# deployment.net
KiCad netlist of a schematic drawn in EAGLE
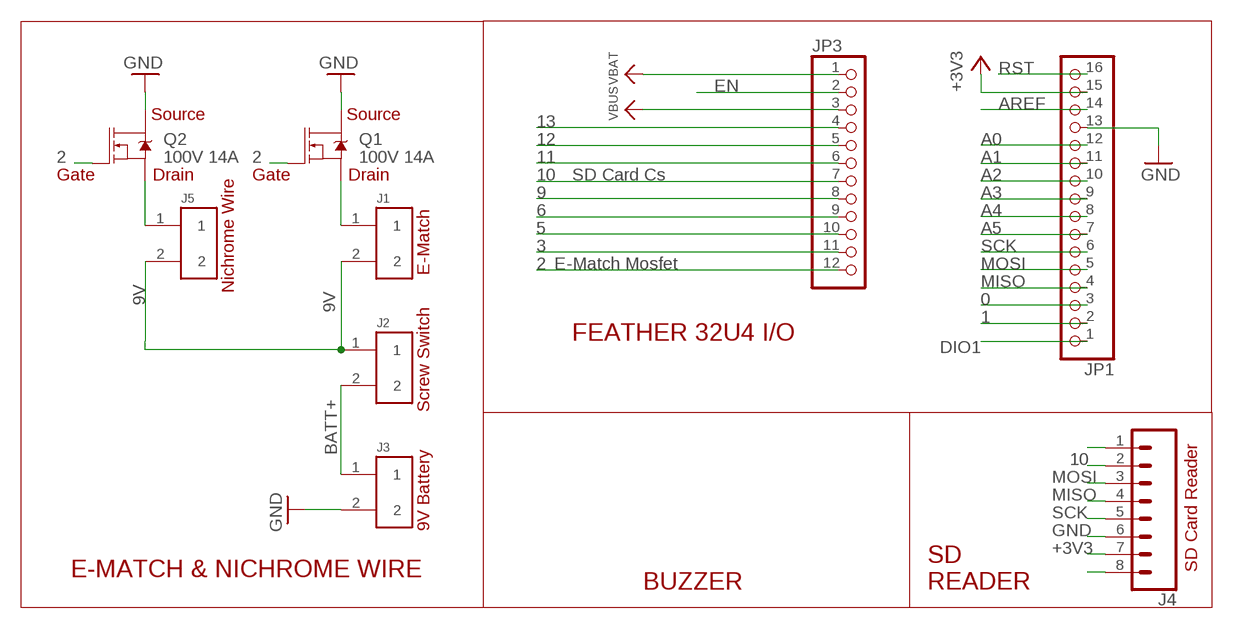
[diagram p0: schematic, sheet 1]

(export (version "E")
  (design (tool "Eeschema 10.0.6"))
  (components
    (comp (ref "J1")
      (value "1935161")
      (footprint "eagle-import:PHOENIX_1935161")
      (fields (field (name "DIGI-KEY_PART_NUMBER") "277-1667-ND") (field (name "MF") "Phoenix Contact"))
      (libsource (lib "eagle-import") (part "1935161"))
    )
    (comp (ref "J2")
      (value "1935161")
      (footprint "eagle-import:PHOENIX_1935161")
      (fields (field (name "DIGI-KEY_PART_NUMBER") "277-1667-ND") (field (name "MF") "Phoenix Contact"))
      (libsource (lib "eagle-import") (part "1935161"))
    )
    (comp (ref "J3")
      (value "1935161")
      (footprint "eagle-import:PHOENIX_1935161")
      (fields (field (name "DIGI-KEY_PART_NUMBER") "277-1667-ND") (field (name "MF") "Phoenix Contact"))
      (libsource (lib "eagle-import") (part "1935161"))
    )
    (comp (ref "J4")
      (value "CONN_08\"")
      (footprint "eagle-import:1X08")
      (libsource (lib "eagle-import") (part "CONN_08{dblquote}"))
    )
    (comp (ref "J5")
      (value "1935161")
      (footprint "eagle-import:PHOENIX_1935161")
      (fields (field (name "DIGI-KEY_PART_NUMBER") "277-1667-ND") (field (name "MF") "Phoenix Contact"))
      (libsource (lib "eagle-import") (part "1935161"))
    )
    (comp (ref "JP1")
      (value "HEADER-1X16ROUND")
      (footprint "eagle-import:1X16_ROUND")
      (libsource (lib "eagle-import") (part "HEADER-1X16ROUND"))
    )
    (comp (ref "JP3")
      (value "HEADER-1X12")
      (footprint "eagle-import:1X12_ROUND")
      (libsource (lib "eagle-import") (part "HEADER-1X12"))
    )
    (comp (ref "Q1")
      (value "100V 14A")
      (footprint "eagle-import:TO220V")
      (libsource (lib "eagle-import") (part "MOSFET-NCH-FQP30N06L"))
    )
    (comp (ref "Q2")
      (value "100V 14A")
      (footprint "eagle-import:TO220V")
      (libsource (lib "eagle-import") (part "MOSFET-NCH-FQP30N06L"))
    )
  )
  (nets
    (net (code "1") (name "+3V3") (class "Default")
      (node (ref "J4") (pin "7") (pinfunction "7_7") (pintype "passive"))
      (node (ref "JP1") (pin "15") (pinfunction "15_15") (pintype "passive"))
    )
    (net (code "2") (name "/0") (class "Default")
      (node (ref "JP1") (pin "3") (pinfunction "3_3") (pintype "passive"))
    )
    (net (code "3") (name "/1") (class "Default")
      (node (ref "JP1") (pin "2") (pinfunction "2_2") (pintype "passive"))
    )
    (net (code "4") (name "/2") (class "Default")
      (node (ref "JP3") (pin "12") (pinfunction "12_12") (pintype "passive"))
      (node (ref "Q1") (pin "1") (pinfunction "G_1") (pintype "bidirectional"))
      (node (ref "Q2") (pin "1") (pinfunction "G_1") (pintype "bidirectional"))
    )
    (net (code "5") (name "/3") (class "Default")
      (node (ref "JP3") (pin "11") (pinfunction "11_11") (pintype "passive"))
    )
    (net (code "6") (name "/5") (class "Default")
      (node (ref "JP3") (pin "10") (pinfunction "10_10") (pintype "passive"))
    )
    (net (code "7") (name "/6") (class "Default")
      (node (ref "JP3") (pin "9") (pinfunction "9_9") (pintype "passive"))
    )
    (net (code "8") (name "/9") (class "Default")
      (node (ref "JP3") (pin "8") (pinfunction "8_8") (pintype "passive"))
    )
    (net (code "9") (name "/9V") (class "Default")
      (node (ref "J1") (pin "2") (pinfunction "2_2") (pintype "passive"))
      (node (ref "J2") (pin "1") (pinfunction "1_1") (pintype "passive"))
      (node (ref "J5") (pin "2") (pinfunction "2_2") (pintype "passive"))
    )
    (net (code "10") (name "/10") (class "Default")
      (node (ref "J4") (pin "1") (pinfunction "1_1") (pintype "passive"))
      (node (ref "J4") (pin "2") (pinfunction "2_2") (pintype "passive"))
      (node (ref "JP3") (pin "7") (pinfunction "7_7") (pintype "passive"))
    )
    (net (code "11") (name "/11") (class "Default")
      (node (ref "JP3") (pin "6") (pinfunction "6_6") (pintype "passive"))
    )
    (net (code "12") (name "/12") (class "Default")
      (node (ref "JP3") (pin "5") (pinfunction "5_5") (pintype "passive"))
    )
    (net (code "13") (name "/13") (class "Default")
      (node (ref "JP3") (pin "4") (pinfunction "4_4") (pintype "passive"))
    )
    (net (code "14") (name "/A0") (class "Default")
      (node (ref "JP1") (pin "12") (pinfunction "12_12") (pintype "passive"))
    )
    (net (code "15") (name "/A1") (class "Default")
      (node (ref "JP1") (pin "11") (pinfunction "11_11") (pintype "passive"))
    )
    (net (code "16") (name "/A2") (class "Default")
      (node (ref "JP1") (pin "10") (pinfunction "10_10") (pintype "passive"))
    )
    (net (code "17") (name "/A3") (class "Default")
      (node (ref "JP1") (pin "9") (pinfunction "9_9") (pintype "passive"))
    )
    (net (code "18") (name "/A4") (class "Default")
      (node (ref "JP1") (pin "8") (pinfunction "8_8") (pintype "passive"))
    )
    (net (code "19") (name "/A5") (class "Default")
      (node (ref "JP1") (pin "7") (pinfunction "7_7") (pintype "passive"))
    )
    (net (code "20") (name "/AREF") (class "Default")
      (node (ref "JP1") (pin "14") (pinfunction "14_14") (pintype "passive"))
    )
    (net (code "21") (name "/BATT+") (class "Default")
      (node (ref "J2") (pin "2") (pinfunction "2_2") (pintype "passive"))
      (node (ref "J3") (pin "1") (pinfunction "1_1") (pintype "passive"))
    )
    (net (code "22") (name "/DIO1") (class "Default")
      (node (ref "JP1") (pin "1") (pinfunction "1_1") (pintype "passive"))
    )
    (net (code "23") (name "/EN") (class "Default")
      (node (ref "JP3") (pin "2") (pinfunction "2_2") (pintype "passive"))
    )
    (net (code "24") (name "/MISO") (class "Default")
      (node (ref "J4") (pin "4") (pinfunction "4_4") (pintype "passive"))
      (node (ref "JP1") (pin "4") (pinfunction "4_4") (pintype "passive"))
    )
    (net (code "25") (name "/MOSI") (class "Default")
      (node (ref "J4") (pin "3") (pinfunction "3_3") (pintype "passive"))
      (node (ref "JP1") (pin "5") (pinfunction "5_5") (pintype "passive"))
    )
    (net (code "26") (name "/RST") (class "Default")
      (node (ref "JP1") (pin "16") (pinfunction "16_16") (pintype "passive"))
    )
    (net (code "27") (name "/SCK") (class "Default")
      (node (ref "J4") (pin "5") (pinfunction "5_5") (pintype "passive"))
      (node (ref "JP1") (pin "6") (pinfunction "6_6") (pintype "passive"))
    )
    (net (code "28") (name "GND") (class "Default")
      (node (ref "J3") (pin "2") (pinfunction "2_2") (pintype "passive"))
      (node (ref "J4") (pin "6") (pinfunction "6_6") (pintype "passive"))
      (node (ref "JP1") (pin "13") (pinfunction "13_13") (pintype "passive"))
      (node (ref "Q1") (pin "2") (pinfunction "D_2") (pintype "bidirectional"))
      (node (ref "Q2") (pin "2") (pinfunction "D_2") (pintype "bidirectional"))
    )
    (net (code "29") (name "Net-(Q1-S)") (class "Default")
      (node (ref "J1") (pin "1") (pinfunction "1_1") (pintype "passive"))
      (node (ref "Q1") (pin "3") (pinfunction "S_3") (pintype "bidirectional"))
    )
    (net (code "30") (name "Net-(Q2-S)") (class "Default")
      (node (ref "J5") (pin "1") (pinfunction "1_1") (pintype "passive"))
      (node (ref "Q2") (pin "3") (pinfunction "S_3") (pintype "bidirectional"))
    )
    (net (code "31") (name "VBAT") (class "Default")
      (node (ref "JP3") (pin "1") (pinfunction "1_1") (pintype "passive"))
    )
    (net (code "32") (name "VBUS") (class "Default")
      (node (ref "JP3") (pin "3") (pinfunction "3_3") (pintype "passive"))
    )
    (net (code "33") (name "unconnected-(J4-Pad8)") (class "Default")
      (node (ref "J4") (pin "8") (pinfunction "8_8") (pintype "passive"))
    )
  )
)
